# version_1.net
KiCad netlist of a schematic drawn in EAGLE
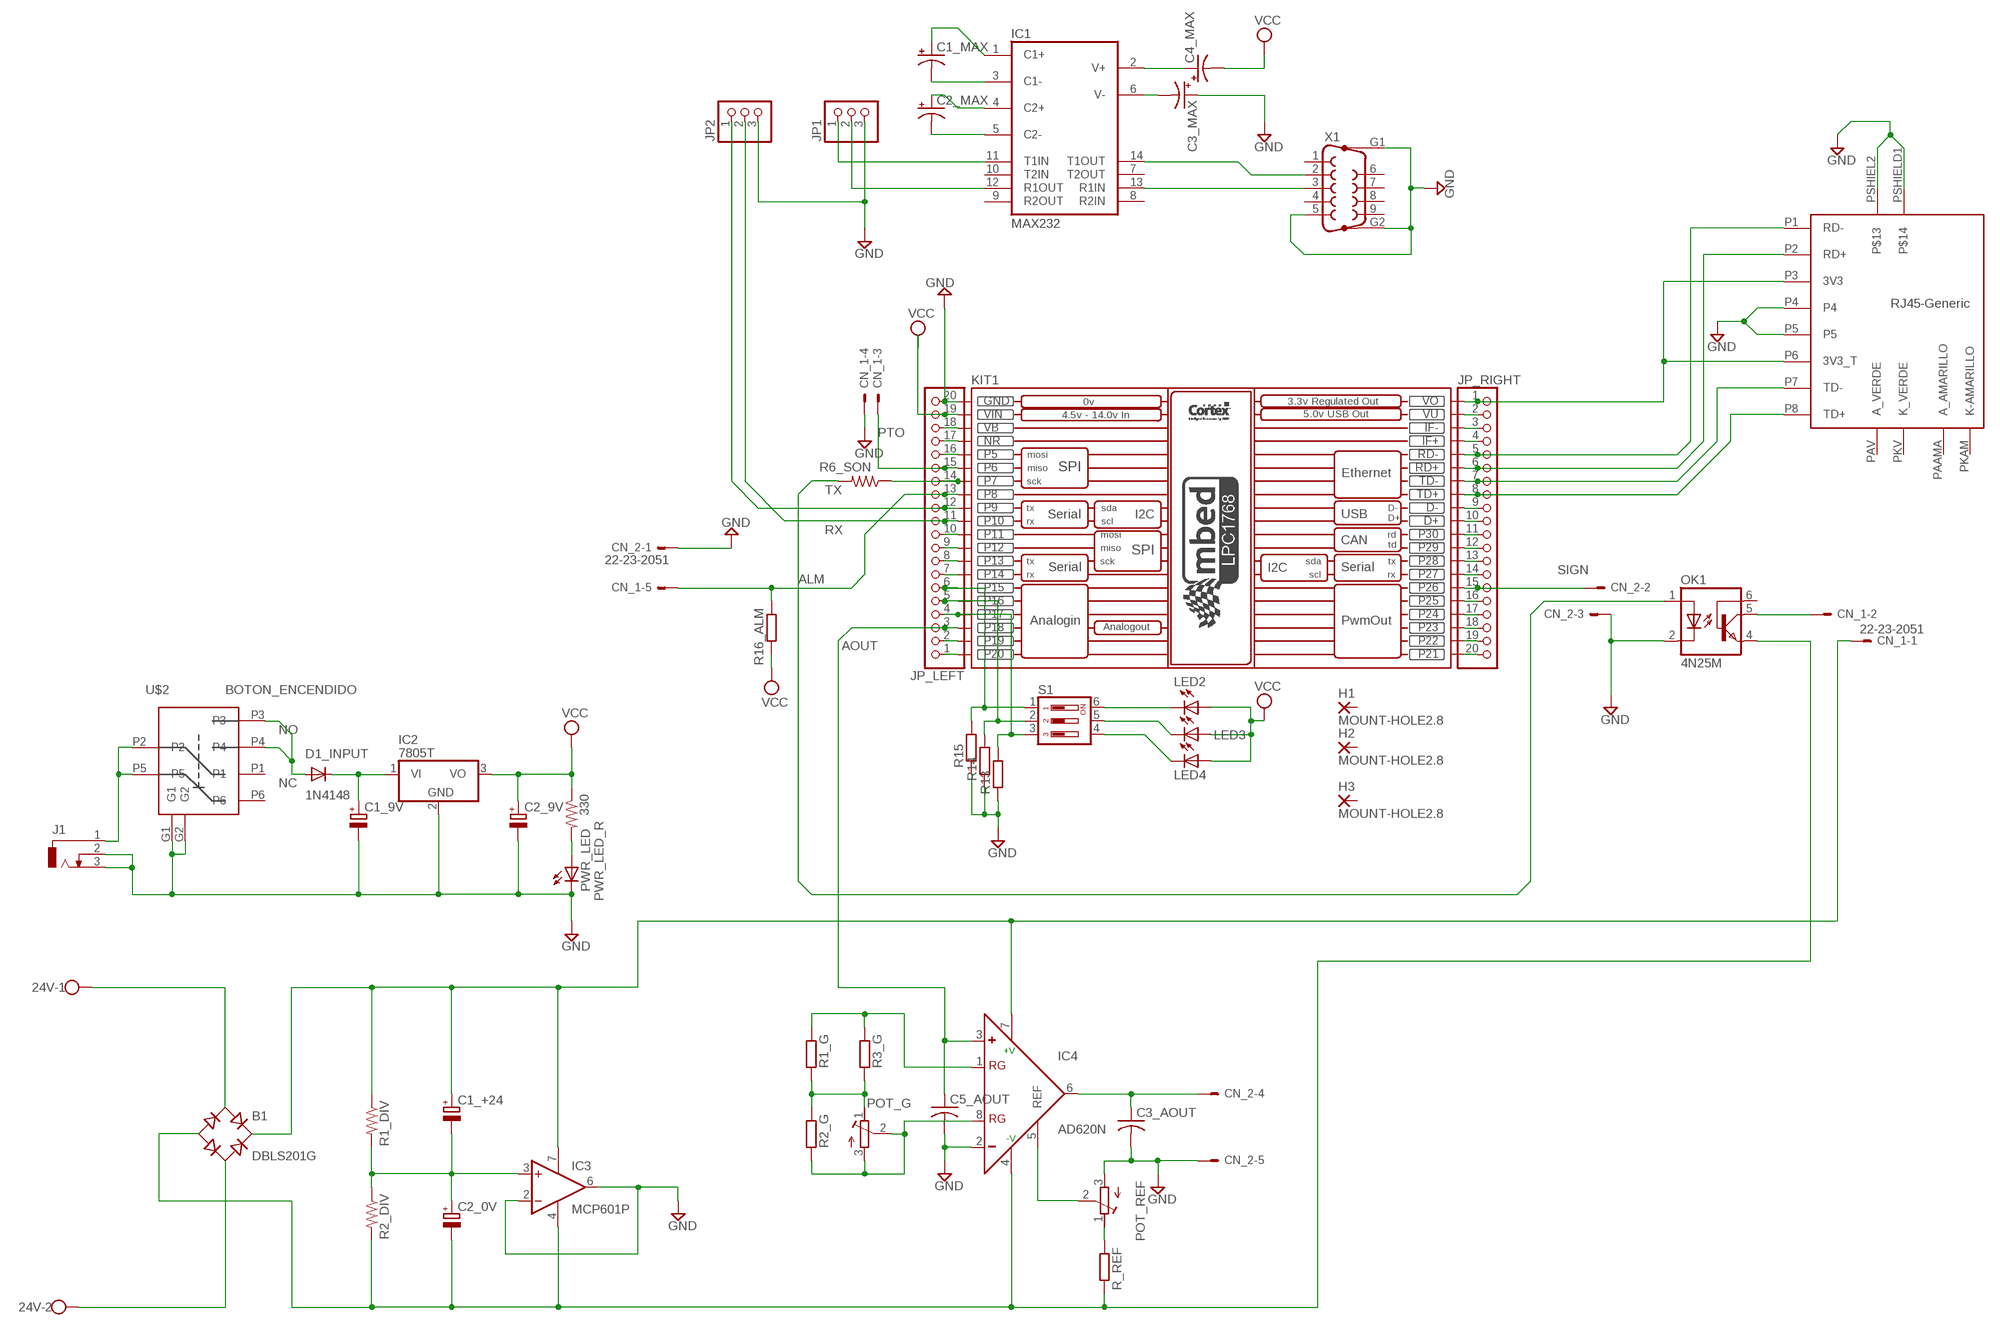
[diagram p0: schematic, sheet 1]

(export (version "E")
  (design (tool "Eeschema 10.0.6"))
  (components
    (comp (ref "24V")
      (value "W237-02P")
      (footprint "eagle-import:W237-132")
      (libsource (lib "eagle-import") (part "W237-02P"))
    )
    (comp (ref "B1")
      (value "DBLS201G")
      (footprint "eagle-import:DBS")
      (libsource (lib "eagle-import") (part "DB?GLS201"))
    )
    (comp (ref "C1_+24")
      (value "CPOL-EUTT5D7")
      (footprint "eagle-import:TT5D7")
      (libsource (lib "eagle-import") (part "CPOL-EUTT5D7"))
    )
    (comp (ref "C1_9V")
      (value "CPOL-EUTT5D7")
      (footprint "eagle-import:TT5D7")
      (libsource (lib "eagle-import") (part "CPOL-EUTT5D7"))
    )
    (comp (ref "C1_MAX")
      (value "CPOL-USE2,5-6E")
      (footprint "eagle-import:E2,5-6E")
      (libsource (lib "eagle-import") (part "CPOL-USE2,5-6E"))
    )
    (comp (ref "C2_0V")
      (value "CPOL-EUTT5D7")
      (footprint "eagle-import:TT5D7")
      (libsource (lib "eagle-import") (part "CPOL-EUTT5D7"))
    )
    (comp (ref "C2_9V")
      (value "CPOL-EUTT5D7")
      (footprint "eagle-import:TT5D7")
      (libsource (lib "eagle-import") (part "CPOL-EUTT5D7"))
    )
    (comp (ref "C2_MAX")
      (value "CPOL-USE2,5-6E")
      (footprint "eagle-import:E2,5-6E")
      (libsource (lib "eagle-import") (part "CPOL-USE2,5-6E"))
    )
    (comp (ref "C3_AOUT")
      (value "C-US025-024X044")
      (footprint "eagle-import:C025-024X044")
      (libsource (lib "eagle-import") (part "C-US025-024X044"))
    )
    (comp (ref "C3_MAX")
      (value "CPOL-USE2,5-6E")
      (footprint "eagle-import:E2,5-6E")
      (libsource (lib "eagle-import") (part "CPOL-USE2,5-6E"))
    )
    (comp (ref "C4_MAX")
      (value "CPOL-USE2,5-6E")
      (footprint "eagle-import:E2,5-6E")
      (libsource (lib "eagle-import") (part "CPOL-USE2,5-6E"))
    )
    (comp (ref "C5_AOUT")
      (value "C-US025-024X044")
      (footprint "eagle-import:C025-024X044")
      (libsource (lib "eagle-import") (part "C-US025-024X044"))
    )
    (comp (ref "CN_1")
      (value "22-23-2051")
      (footprint "eagle-import:22-23-2051")
      (libsource (lib "eagle-import") (part "22-23-2051"))
    )
    (comp (ref "CN_2")
      (value "22-23-2051")
      (footprint "eagle-import:22-23-2051")
      (libsource (lib "eagle-import") (part "22-23-2051"))
    )
    (comp (ref "D1_INPUT")
      (value "1N4148")
      (footprint "eagle-import:DO35-10")
      (libsource (lib "eagle-import") (part "1N4148DO35-10"))
    )
    (comp (ref "H1")
      (value "MOUNT-HOLE2.8")
      (footprint "eagle-import:2,54_0,8")
      (libsource (lib "eagle-import") (part "2,54/0,8"))
    )
    (comp (ref "H2")
      (value "MOUNT-HOLE2.8")
      (footprint "eagle-import:2,54_0,8")
      (libsource (lib "eagle-import") (part "2,54/0,8"))
    )
    (comp (ref "H3")
      (value "MOUNT-HOLE2.8")
      (footprint "eagle-import:2,54_0,8")
      (libsource (lib "eagle-import") (part "2,54/0,8"))
    )
    (comp (ref "IC1")
      (value "MAX232")
      (footprint "eagle-import:DIL16")
      (libsource (lib "eagle-import") (part "MAX232"))
    )
    (comp (ref "IC2")
      (value "7805T")
      (footprint "eagle-import:TO220H")
      (libsource (lib "eagle-import") (part "78T05"))
    )
    (comp (ref "IC3")
      (value "MCP601P")
      (footprint "eagle-import:DIL08")
      (libsource (lib "eagle-import") (part "MCP601P"))
    )
    (comp (ref "IC4")
      (value "AD620N")
      (footprint "eagle-import:DIL08")
      (libsource (lib "eagle-import") (part "AD620N"))
    )
    (comp (ref "J1")
      (value "DCJ0303")
      (footprint "eagle-import:DCJ0303")
      (libsource (lib "eagle-import") (part "DCJ0303"))
    )
    (comp (ref "JP1")
      (value "PINHD-1X3")
      (footprint "eagle-import:1X03")
      (libsource (lib "eagle-import") (part "PINHD-1X3"))
    )
    (comp (ref "JP2")
      (value "PINHD-1X3")
      (footprint "eagle-import:1X03")
      (libsource (lib "eagle-import") (part "PINHD-1X3"))
    )
    (comp (ref "JP_LEFT")
      (value "PINHD-1X20")
      (footprint "eagle-import:1X20")
      (libsource (lib "eagle-import") (part "PINHD-1X20"))
    )
    (comp (ref "JP_RIGHT")
      (value "PINHD-1X20")
      (footprint "eagle-import:1X20")
      (libsource (lib "eagle-import") (part "PINHD-1X20"))
    )
    (comp (ref "KIT1")
      (value "MBED_NXP_LPC1768")
      (footprint "eagle-import:MBED-KIT")
      (libsource (lib "eagle-import") (part "MBED_NXP_LPC1768"))
    )
    (comp (ref "LED2")
      (value "LED3MM")
      (footprint "eagle-import:LED3MM")
      (libsource (lib "eagle-import") (part "LED3MM"))
    )
    (comp (ref "LED3")
      (value "LED3MM")
      (footprint "eagle-import:LED3MM")
      (libsource (lib "eagle-import") (part "LED3MM"))
    )
    (comp (ref "LED4")
      (value "LED3MM")
      (footprint "eagle-import:LED3MM")
      (libsource (lib "eagle-import") (part "LED3MM"))
    )
    (comp (ref "OK1")
      (value "4N25M")
      (footprint "eagle-import:DIL06")
      (libsource (lib "eagle-import") (part "4N?M25"))
    )
    (comp (ref "POT_G")
      (value "R-TRIMMT93XB")
      (footprint "eagle-import:RTRIMT93XB")
      (libsource (lib "eagle-import") (part "R-TRIMMT93XB"))
    )
    (comp (ref "POT_REF")
      (value "R-TRIMMT93XB")
      (footprint "eagle-import:RTRIMT93XB")
      (libsource (lib "eagle-import") (part "R-TRIMMT93XB"))
    )
    (comp (ref "PWR_LED")
      (value "LED3MM")
      (footprint "eagle-import:LED3MM")
      (libsource (lib "eagle-import") (part "LED3MM"))
    )
    (comp (ref "PWR_LED_R")
      (value "330")
      (footprint "eagle-import:0207_15")
      (libsource (lib "eagle-import") (part "R-US_0207/15"))
    )
    (comp (ref "R1_DIV")
      (value "R-US_0207/10")
      (footprint "eagle-import:0207_10")
      (libsource (lib "eagle-import") (part "resistor_R-US_0207/10"))
    )
    (comp (ref "R1_G")
      (value "R-EU_0207/2V")
      (footprint "eagle-import:0207_2V")
      (libsource (lib "eagle-import") (part "R-EU_0207/2V"))
    )
    (comp (ref "R2_DIV")
      (value "R-US_0207/10")
      (footprint "eagle-import:0207_10")
      (libsource (lib "eagle-import") (part "resistor_R-US_0207/10"))
    )
    (comp (ref "R2_G")
      (value "R-EU_0207/2V")
      (footprint "eagle-import:0207_2V")
      (libsource (lib "eagle-import") (part "R-EU_0207/2V"))
    )
    (comp (ref "R3_G")
      (value "R-EU_0207/2V")
      (footprint "eagle-import:0207_2V")
      (libsource (lib "eagle-import") (part "R-EU_0207/2V"))
    )
    (comp (ref "R6_SON")
      (value "R-US_0207/7")
      (footprint "eagle-import:0207_7")
      (libsource (lib "eagle-import") (part "R-US_0207/7"))
    )
    (comp (ref "R13")
      (value "R-EU_0207/15")
      (footprint "eagle-import:0207_15")
      (libsource (lib "eagle-import") (part "R-EU_0207/15"))
    )
    (comp (ref "R14")
      (value "R-EU_0207/15")
      (footprint "eagle-import:0207_15")
      (libsource (lib "eagle-import") (part "R-EU_0207/15"))
    )
    (comp (ref "R15")
      (value "R-EU_0207/15")
      (footprint "eagle-import:0207_15")
      (libsource (lib "eagle-import") (part "R-EU_0207/15"))
    )
    (comp (ref "R16_ALM")
      (value "R-EU_0207/12")
      (footprint "eagle-import:0207_12")
      (libsource (lib "eagle-import") (part "R-EU_0207/12"))
    )
    (comp (ref "R_REF")
      (value "R-EU_0207/2V")
      (footprint "eagle-import:0207_2V")
      (libsource (lib "eagle-import") (part "R-EU_0207/2V"))
    )
    (comp (ref "S1")
      (value "DIP03YL")
      (footprint "eagle-import:DIP03YL")
      (libsource (lib "eagle-import") (part "DIP03YL"))
    )
    (comp (ref "U$1")
      (value "RJ-45-GENERIC")
      (footprint "eagle-import:RJ45-GENERIC")
      (libsource (lib "eagle-import") (part "RJ-45-GENERIC"))
    )
    (comp (ref "U$2")
      (value "BOTON_ENCENDIDO")
      (footprint "eagle-import:BOTON_ENCNEDIDO")
      (libsource (lib "eagle-import") (part "BOTON_ENCENDIDO"))
    )
    (comp (ref "X1")
      (value "F09HP")
      (footprint "eagle-import:F09HP")
      (libsource (lib "eagle-import") (part "F09HP"))
    )
  )
  (nets
    (net (code "1") (name "/ALM") (class "Default")
      (node (ref "CN_1") (pin "5") (pinfunction "S_5") (pintype "passive"))
      (node (ref "JP_LEFT") (pin "13") (pinfunction "13_13") (pintype "passive"))
      (node (ref "KIT1") (pin "P$8") (pinfunction "P8_P$8") (pintype "bidirectional"))
      (node (ref "R16_ALM") (pin "1") (pinfunction "1_1") (pintype "passive"))
    )
    (net (code "2") (name "/AOUT") (class "Default")
      (node (ref "C5_AOUT") (pin "1") (pinfunction "1_1") (pintype "passive"))
      (node (ref "IC4") (pin "3") (pinfunction "+_3") (pintype "input"))
      (node (ref "JP_LEFT") (pin "3") (pinfunction "3_3") (pintype "passive"))
      (node (ref "KIT1") (pin "P$18") (pinfunction "P18_P$18") (pintype "bidirectional"))
    )
    (net (code "3") (name "/PTO") (class "Default")
      (node (ref "CN_1") (pin "3") (pinfunction "S_3") (pintype "passive"))
      (node (ref "JP_LEFT") (pin "15") (pinfunction "15_15") (pintype "passive"))
      (node (ref "KIT1") (pin "P$6") (pinfunction "P6_P$6") (pintype "bidirectional"))
    )
    (net (code "4") (name "/RX") (class "Default")
      (node (ref "JP2") (pin "2") (pinfunction "2_2") (pintype "passive"))
      (node (ref "JP_LEFT") (pin "11") (pinfunction "11_11") (pintype "passive"))
      (node (ref "KIT1") (pin "P$10") (pinfunction "P10_P$10") (pintype "bidirectional"))
    )
    (net (code "5") (name "/SIGN") (class "Default")
      (node (ref "CN_2") (pin "2") (pinfunction "S_2") (pintype "passive"))
      (node (ref "JP_RIGHT") (pin "15") (pinfunction "15_15") (pintype "passive"))
      (node (ref "KIT1") (pin "P$26") (pinfunction "P26_P$26") (pintype "bidirectional"))
    )
    (net (code "6") (name "/TX") (class "Default")
      (node (ref "JP2") (pin "1") (pinfunction "1_1") (pintype "passive"))
      (node (ref "JP_LEFT") (pin "12") (pinfunction "12_12") (pintype "passive"))
      (node (ref "KIT1") (pin "P$9") (pinfunction "P9_P$9") (pintype "bidirectional"))
    )
    (net (code "7") (name "GND") (class "Default")
      (node (ref "C1_9V") (pin "-") (pinfunction "-_-") (pintype "passive"))
      (node (ref "C2_9V") (pin "-") (pinfunction "-_-") (pintype "passive"))
      (node (ref "C3_AOUT") (pin "2") (pinfunction "2_2") (pintype "passive"))
      (node (ref "C3_MAX") (pin "+") (pinfunction "+_+") (pintype "passive"))
      (node (ref "C5_AOUT") (pin "2") (pinfunction "2_2") (pintype "passive"))
      (node (ref "CN_1") (pin "4") (pinfunction "S_4") (pintype "passive"))
      (node (ref "CN_2") (pin "1") (pinfunction "S_1") (pintype "passive"))
      (node (ref "CN_2") (pin "3") (pinfunction "S_3") (pintype "passive"))
      (node (ref "CN_2") (pin "5") (pinfunction "S_5") (pintype "passive"))
      (node (ref "IC2") (pin "2") (pinfunction "GND_2") (pintype "passive"))
      (node (ref "IC3") (pin "2") (pinfunction "-IN_2") (pintype "input"))
      (node (ref "IC3") (pin "6") (pinfunction "OUT_6") (pintype "output"))
      (node (ref "IC4") (pin "2") (pinfunction "-_2") (pintype "input"))
      (node (ref "J1") (pin "2") (pinfunction "2_2") (pintype "passive"))
      (node (ref "J1") (pin "3") (pinfunction "3_3") (pintype "passive"))
      (node (ref "JP1") (pin "3") (pinfunction "3_3") (pintype "passive"))
      (node (ref "JP2") (pin "3") (pinfunction "3_3") (pintype "passive"))
      (node (ref "JP_LEFT") (pin "20") (pinfunction "20_20") (pintype "passive"))
      (node (ref "KIT1") (pin "GND") (pinfunction "GND_GND") (pintype "power_in"))
      (node (ref "OK1") (pin "2") (pinfunction "C_2") (pintype "passive"))
      (node (ref "POT_REF") (pin "3") (pinfunction "E_3") (pintype "passive"))
      (node (ref "PWR_LED") (pin "K") (pinfunction "C_K") (pintype "passive"))
      (node (ref "R13") (pin "1") (pinfunction "1_1") (pintype "passive"))
      (node (ref "R14") (pin "1") (pinfunction "1_1") (pintype "passive"))
      (node (ref "R15") (pin "1") (pinfunction "1_1") (pintype "passive"))
      (node (ref "U$1") (pin "P4") (pinfunction "P4_P4") (pintype "bidirectional"))
      (node (ref "U$1") (pin "P5") (pinfunction "P5_P5") (pintype "bidirectional"))
      (node (ref "U$1") (pin "PSHIEL2") (pinfunction "P$13_PSHIEL2") (pintype "bidirectional"))
      (node (ref "U$1") (pin "PSHIELD1") (pinfunction "P$14_PSHIELD1") (pintype "bidirectional"))
      (node (ref "U$2") (pin "G1") (pinfunction "G1_G1") (pintype "bidirectional"))
      (node (ref "U$2") (pin "G2") (pinfunction "G2_G2") (pintype "bidirectional"))
      (node (ref "X1") (pin "5") (pinfunction "5_5") (pintype "passive"))
      (node (ref "X1") (pin "G1") (pinfunction "G1_G1") (pintype "passive"))
      (node (ref "X1") (pin "G2") (pinfunction "G2_G2") (pintype "passive"))
    )
    (net (code "8") (name "Net-(24VA-KL)") (class "Default")
      (node (ref "24V") (pin "1") (pinfunction "KL_1") (pintype "passive"))
      (node (ref "B1") (pin "AC1") (pinfunction "AC1_AC1") (pintype "passive"))
    )
    (net (code "9") (name "Net-(24VB-KL)") (class "Default")
      (node (ref "24V") (pin "2") (pinfunction "KL_2") (pintype "passive"))
      (node (ref "B1") (pin "AC2") (pinfunction "AC2_AC2") (pintype "passive"))
    )
    (net (code "10") (name "Net-(CN_1A-S)") (class "Default")
      (node (ref "B1") (pin "+") (pinfunction "+_+") (pintype "passive"))
      (node (ref "C1_+24") (pin "+") (pinfunction "+_+") (pintype "passive"))
      (node (ref "CN_1") (pin "1") (pinfunction "S_1") (pintype "passive"))
      (node (ref "IC3") (pin "7") (pinfunction "V+_7") (pintype "power_in"))
      (node (ref "IC4") (pin "7") (pinfunction "+V_7") (pintype "power_in"))
      (node (ref "R1_DIV") (pin "1") (pinfunction "1_1") (pintype "passive"))
    )
    (net (code "11") (name "Net-(CN_1B-S)") (class "Default")
      (node (ref "CN_1") (pin "2") (pinfunction "S_2") (pintype "passive"))
      (node (ref "OK1") (pin "5") (pinfunction "COL_5") (pintype "passive"))
    )
    (net (code "12") (name "Net-(CN_2D-S)") (class "Default")
      (node (ref "C3_AOUT") (pin "1") (pinfunction "1_1") (pintype "passive"))
      (node (ref "CN_2") (pin "4") (pinfunction "S_4") (pintype "passive"))
      (node (ref "IC4") (pin "6") (pinfunction "OUT_6") (pintype "output"))
    )
    (net (code "13") (name "Net-(D1_INPUT-PadA)") (class "Default")
      (node (ref "D1_INPUT") (pin "A") (pinfunction "A_A") (pintype "passive"))
      (node (ref "U$2") (pin "P3") (pinfunction "P3_P3") (pintype "bidirectional"))
      (node (ref "U$2") (pin "P4") (pinfunction "P4_P4") (pintype "bidirectional"))
    )
    (net (code "14") (name "Net-(IC1A-C1+)") (class "Default")
      (node (ref "C1_MAX") (pin "+") (pinfunction "+_+") (pintype "passive"))
      (node (ref "IC1") (pin "1") (pinfunction "C1+_1") (pintype "bidirectional"))
    )
    (net (code "15") (name "Net-(IC1A-C1-)") (class "Default")
      (node (ref "C1_MAX") (pin "-") (pinfunction "-_-") (pintype "passive"))
      (node (ref "IC1") (pin "3") (pinfunction "C1-_3") (pintype "bidirectional"))
    )
    (net (code "16") (name "Net-(IC1A-C2+)") (class "Default")
      (node (ref "C2_MAX") (pin "+") (pinfunction "+_+") (pintype "passive"))
      (node (ref "IC1") (pin "4") (pinfunction "C2+_4") (pintype "bidirectional"))
    )
    (net (code "17") (name "Net-(IC1A-C2-)") (class "Default")
      (node (ref "C2_MAX") (pin "-") (pinfunction "-_-") (pintype "passive"))
      (node (ref "IC1") (pin "5") (pinfunction "C2-_5") (pintype "bidirectional"))
    )
    (net (code "18") (name "Net-(IC1A-R1IN)") (class "Default")
      (node (ref "IC1") (pin "13") (pinfunction "R1IN_13") (pintype "input"))
      (node (ref "X1") (pin "3") (pinfunction "3_3") (pintype "passive"))
    )
    (net (code "19") (name "Net-(IC1A-R1OUT)") (class "Default")
      (node (ref "IC1") (pin "12") (pinfunction "R1OUT_12") (pintype "output"))
      (node (ref "JP1") (pin "2") (pinfunction "2_2") (pintype "passive"))
    )
    (net (code "20") (name "Net-(IC1A-T1IN)") (class "Default")
      (node (ref "IC1") (pin "11") (pinfunction "T1IN_11") (pintype "input"))
      (node (ref "JP1") (pin "1") (pinfunction "1_1") (pintype "passive"))
    )
    (net (code "21") (name "Net-(IC1A-T1OUT)") (class "Default")
      (node (ref "IC1") (pin "14") (pinfunction "T1OUT_14") (pintype "output"))
      (node (ref "X1") (pin "2") (pinfunction "2_2") (pintype "passive"))
    )
    (net (code "22") (name "Net-(IC1A-V+)") (class "Default")
      (node (ref "C4_MAX") (pin "+") (pinfunction "+_+") (pintype "passive"))
      (node (ref "IC1") (pin "2") (pinfunction "V+_2") (pintype "bidirectional"))
    )
    (net (code "23") (name "Net-(IC1A-V-)") (class "Default")
      (node (ref "C3_MAX") (pin "-") (pinfunction "-_-") (pintype "passive"))
      (node (ref "IC1") (pin "6") (pinfunction "V-_6") (pintype "bidirectional"))
    )
    (net (code "24") (name "Net-(IC2-VI)") (class "Default")
      (node (ref "C1_9V") (pin "+") (pinfunction "+_+") (pintype "passive"))
      (node (ref "D1_INPUT") (pin "C") (pinfunction "C_C") (pintype "passive"))
      (node (ref "IC2") (pin "1") (pinfunction "VI_1") (pintype "input"))
    )
    (net (code "25") (name "Net-(IC3-+IN)") (class "Default")
      (node (ref "C1_+24") (pin "-") (pinfunction "-_-") (pintype "passive"))
      (node (ref "C2_0V") (pin "+") (pinfunction "+_+") (pintype "passive"))
      (node (ref "IC3") (pin "3") (pinfunction "+IN_3") (pintype "input"))
      (node (ref "R1_DIV") (pin "2") (pinfunction "2_2") (pintype "passive"))
      (node (ref "R2_DIV") (pin "1") (pinfunction "1_1") (pintype "passive"))
    )
    (net (code "26") (name "Net-(IC3-V-)") (class "Default")
      (node (ref "B1") (pin "-") (pinfunction "-_-") (pintype "passive"))
      (node (ref "C2_0V") (pin "-") (pinfunction "-_-") (pintype "passive"))
      (node (ref "IC3") (pin "4") (pinfunction "V-_4") (pintype "power_in"))
      (node (ref "IC4") (pin "4") (pinfunction "-V_4") (pintype "power_in"))
      (node (ref "OK1") (pin "4") (pinfunction "EMI_4") (pintype "passive"))
      (node (ref "R2_DIV") (pin "2") (pinfunction "2_2") (pintype "passive"))
      (node (ref "R_REF") (pin "2") (pinfunction "2_2") (pintype "passive"))
    )
    (net (code "27") (name "Net-(IC4-REF)") (class "Default")
      (node (ref "IC4") (pin "5") (pinfunction "REF_5") (pintype "passive"))
      (node (ref "POT_REF") (pin "2") (pinfunction "S_2") (pintype "passive"))
    )
    (net (code "28") (name "Net-(IC4-RG-Pad1)") (class "Default")
      (node (ref "IC4") (pin "1") (pinfunction "RG_1") (pintype "passive"))
      (node (ref "R1_G") (pin "1") (pinfunction "1_1") (pintype "passive"))
      (node (ref "R3_G") (pin "1") (pinfunction "1_1") (pintype "passive"))
    )
    (net (code "29") (name "Net-(J1-Pad1)") (class "Default")
      (node (ref "J1") (pin "1") (pinfunction "1_1") (pintype "passive"))
      (node (ref "U$2") (pin "P2") (pinfunction "P2_P2") (pintype "bidirectional"))
      (node (ref "U$2") (pin "P5") (pinfunction "P5_P5") (pintype "bidirectional"))
    )
    (net (code "30") (name "Net-(JP_LEFT-Pad17)") (class "Default")
      (node (ref "JP_LEFT") (pin "17") (pinfunction "17_17") (pintype "passive"))
      (node (ref "KIT1") (pin "NR") (pinfunction "NR_NR") (pintype "power_in"))
    )
    (net (code "31") (name "Net-(JP_LEFT-Pad18)") (class "Default")
      (node (ref "JP_LEFT") (pin "18") (pinfunction "18_18") (pintype "passive"))
      (node (ref "KIT1") (pin "VB") (pinfunction "VB_VB") (pintype "power_in"))
    )
    (net (code "32") (name "Net-(JP_RIGHT-Pad2)") (class "Default")
      (node (ref "JP_RIGHT") (pin "2") (pinfunction "2_2") (pintype "passive"))
      (node (ref "KIT1") (pin "VU") (pinfunction "VU_VU") (pintype "power_in"))
    )
    (net (code "33") (name "Net-(JP_RIGHT-Pad3)") (class "Default")
      (node (ref "JP_RIGHT") (pin "3") (pinfunction "3_3") (pintype "passive"))
      (node (ref "KIT1") (pin "IF-") (pinfunction "IF-_IF-") (pintype "bidirectional"))
    )
    (net (code "34") (name "Net-(JP_RIGHT-Pad4)") (class "Default")
      (node (ref "JP_RIGHT") (pin "4") (pinfunction "4_4") (pintype "passive"))
      (node (ref "KIT1") (pin "IF+") (pinfunction "IF+_IF+") (pintype "bidirectional"))
    )
    (net (code "35") (name "Net-(JP_RIGHT-Pad9)") (class "Default")
      (node (ref "JP_RIGHT") (pin "9") (pinfunction "9_9") (pintype "passive"))
      (node (ref "KIT1") (pin "D-") (pinfunction "D-_D-") (pintype "bidirectional"))
    )
    (net (code "36") (name "Net-(JP_RIGHT-Pad10)") (class "Default")
      (node (ref "JP_RIGHT") (pin "10") (pinfunction "10_10") (pintype "passive"))
      (node (ref "KIT1") (pin "D+") (pinfunction "D+_D+") (pintype "bidirectional"))
    )
    (net (code "37") (name "Net-(KIT1-P5)") (class "Default")
      (node (ref "JP_LEFT") (pin "16") (pinfunction "16_16") (pintype "passive"))
      (node (ref "KIT1") (pin "P$5") (pinfunction "P5_P$5") (pintype "bidirectional"))
    )
    (net (code "38") (name "Net-(KIT1-P7)") (class "Default")
      (node (ref "JP_LEFT") (pin "14") (pinfunction "14_14") (pintype "passive"))
      (node (ref "KIT1") (pin "P$7") (pinfunction "P7_P$7") (pintype "bidirectional"))
      (node (ref "R6_SON") (pin "1") (pinfunction "1_1") (pintype "passive"))
    )
    (net (code "39") (name "Net-(KIT1-P11)") (class "Default")
      (node (ref "JP_LEFT") (pin "10") (pinfunction "10_10") (pintype "passive"))
      (node (ref "KIT1") (pin "P$11") (pinfunction "P11_P$11") (pintype "bidirectional"))
    )
    (net (code "40") (name "Net-(KIT1-P12)") (class "Default")
      (node (ref "JP_LEFT") (pin "9") (pinfunction "9_9") (pintype "passive"))
      (node (ref "KIT1") (pin "P$12") (pinfunction "P12_P$12") (pintype "bidirectional"))
    )
    (net (code "41") (name "Net-(KIT1-P13)") (class "Default")
      (node (ref "JP_LEFT") (pin "8") (pinfunction "8_8") (pintype "passive"))
      (node (ref "KIT1") (pin "P$13") (pinfunction "P13_P$13") (pintype "bidirectional"))
    )
    (net (code "42") (name "Net-(KIT1-P14)") (class "Default")
      (node (ref "JP_LEFT") (pin "7") (pinfunction "7_7") (pintype "passive"))
      (node (ref "KIT1") (pin "P$14") (pinfunction "P14_P$14") (pintype "bidirectional"))
    )
    (net (code "43") (name "Net-(KIT1-P15)") (class "Default")
      (node (ref "JP_LEFT") (pin "6") (pinfunction "6_6") (pintype "passive"))
      (node (ref "KIT1") (pin "P$15") (pinfunction "P15_P$15") (pintype "bidirectional"))
      (node (ref "R15") (pin "2") (pinfunction "2_2") (pintype "passive"))
      (node (ref "S1") (pin "1") (pinfunction "1_1") (pintype "passive"))
    )
    (net (code "44") (name "Net-(KIT1-P16)") (class "Default")
      (node (ref "JP_LEFT") (pin "5") (pinfunction "5_5") (pintype "passive"))
      (node (ref "KIT1") (pin "P$16") (pinfunction "P16_P$16") (pintype "bidirectional"))
      (node (ref "R14") (pin "2") (pinfunction "2_2") (pintype "passive"))
      (node (ref "S1") (pin "2") (pinfunction "2_2") (pintype "passive"))
    )
    (net (code "45") (name "Net-(KIT1-P17)") (class "Default")
      (node (ref "JP_LEFT") (pin "4") (pinfunction "4_4") (pintype "passive"))
      (node (ref "KIT1") (pin "P$17") (pinfunction "P17_P$17") (pintype "bidirectional"))
      (node (ref "R13") (pin "2") (pinfunction "2_2") (pintype "passive"))
      (node (ref "S1") (pin "3") (pinfunction "3_3") (pintype "passive"))
    )
    (net (code "46") (name "Net-(KIT1-P19)") (class "Default")
      (node (ref "JP_LEFT") (pin "2") (pinfunction "2_2") (pintype "passive"))
      (node (ref "KIT1") (pin "P$19") (pinfunction "P19_P$19") (pintype "bidirectional"))
    )
    (net (code "47") (name "Net-(KIT1-P20)") (class "Default")
      (node (ref "JP_LEFT") (pin "1") (pinfunction "1_1") (pintype "passive"))
      (node (ref "KIT1") (pin "P$20") (pinfunction "P20_P$20") (pintype "bidirectional"))
    )
    (net (code "48") (name "Net-(KIT1-P21)") (class "Default")
      (node (ref "JP_RIGHT") (pin "20") (pinfunction "20_20") (pintype "passive"))
      (node (ref "KIT1") (pin "P$21") (pinfunction "P21_P$21") (pintype "bidirectional"))
    )
    (net (code "49") (name "Net-(KIT1-P22)") (class "Default")
      (node (ref "JP_RIGHT") (pin "19") (pinfunction "19_19") (pintype "passive"))
      (node (ref "KIT1") (pin "P$22") (pinfunction "P22_P$22") (pintype "bidirectional"))
    )
    (net (code "50") (name "Net-(KIT1-P23)") (class "Default")
      (node (ref "JP_RIGHT") (pin "18") (pinfunction "18_18") (pintype "passive"))
      (node (ref "KIT1") (pin "P$23") (pinfunction "P23_P$23") (pintype "bidirectional"))
    )
    (net (code "51") (name "Net-(KIT1-P24)") (class "Default")
      (node (ref "JP_RIGHT") (pin "17") (pinfunction "17_17") (pintype "passive"))
      (node (ref "KIT1") (pin "P$24") (pinfunction "P24_P$24") (pintype "bidirectional"))
    )
    (net (code "52") (name "Net-(KIT1-P25)") (class "Default")
      (node (ref "JP_RIGHT") (pin "16") (pinfunction "16_16") (pintype "passive"))
      (node (ref "KIT1") (pin "P$25") (pinfunction "P25_P$25") (pintype "bidirectional"))
    )
    (net (code "53") (name "Net-(KIT1-P27)") (class "Default")
      (node (ref "JP_RIGHT") (pin "14") (pinfunction "14_14") (pintype "passive"))
      (node (ref "KIT1") (pin "P$27") (pinfunction "P27_P$27") (pintype "bidirectional"))
    )
    (net (code "54") (name "Net-(KIT1-P28)") (class "Default")
      (node (ref "JP_RIGHT") (pin "13") (pinfunction "13_13") (pintype "passive"))
      (node (ref "KIT1") (pin "P$28") (pinfunction "P28_P$28") (pintype "bidirectional"))
    )
    (net (code "55") (name "Net-(KIT1-P29)") (class "Default")
      (node (ref "JP_RIGHT") (pin "12") (pinfunction "12_12") (pintype "passive"))
      (node (ref "KIT1") (pin "P$29") (pinfunction "P29_P$29") (pintype "bidirectional"))
    )
    (net (code "56") (name "Net-(KIT1-P30)") (class "Default")
      (node (ref "JP_RIGHT") (pin "11") (pinfunction "11_11") (pintype "passive"))
      (node (ref "KIT1") (pin "P$30") (pinfunction "P30_P$30") (pintype "bidirectional"))
    )
    (net (code "57") (name "Net-(KIT1-VO)") (class "Default")
      (node (ref "JP_RIGHT") (pin "1") (pinfunction "1_1") (pintype "passive"))
      (node (ref "KIT1") (pin "VOUT") (pinfunction "VO_VOUT") (pintype "power_in"))
      (node (ref "U$1") (pin "P3") (pinfunction "3V3_P3") (pintype "bidirectional"))
      (node (ref "U$1") (pin "P6") (pinfunction "3V3_T_P6") (pintype "bidirectional"))
    )
    (net (code "58") (name "Net-(LED2-C)") (class "Default")
      (node (ref "LED2") (pin "K") (pinfunction "C_K") (pintype "passive"))
      (node (ref "S1") (pin "6") (pinfunction "6_6") (pintype "passive"))
    )
    (net (code "59") (name "Net-(LED3-C)") (class "Default")
      (node (ref "LED3") (pin "K") (pinfunction "C_K") (pintype "passive"))
      (node (ref "S1") (pin "5") (pinfunction "5_5") (pintype "passive"))
    )
    (net (code "60") (name "Net-(LED4-C)") (class "Default")
      (node (ref "LED4") (pin "K") (pinfunction "C_K") (pintype "passive"))
      (node (ref "S1") (pin "4") (pinfunction "4_4") (pintype "passive"))
    )
    (net (code "61") (name "Net-(OK1-A)") (class "Default")
      (node (ref "OK1") (pin "1") (pinfunction "A_1") (pintype "passive"))
      (node (ref "R6_SON") (pin "2") (pinfunction "2_2") (pintype "passive"))
    )
    (net (code "62") (name "Net-(POT_G-A)") (class "Default")
      (node (ref "POT_G") (pin "1") (pinfunction "A_1") (pintype "passive"))
      (node (ref "R1_G") (pin "2") (pinfunction "2_2") (pintype "passive"))
      (node (ref "R2_G") (pin "1") (pinfunction "1_1") (pintype "passive"))
      (node (ref "R3_G") (pin "2") (pinfunction "2_2") (pintype "passive"))
    )
    (net (code "63") (name "Net-(POT_G-E)") (class "Default")
      (node (ref "IC4") (pin "8") (pinfunction "RG_8") (pintype "passive"))
      (node (ref "POT_G") (pin "2") (pinfunction "S_2") (pintype "passive"))
      (node (ref "POT_G") (pin "3") (pinfunction "E_3") (pintype "passive"))
      (node (ref "R2_G") (pin "2") (pinfunction "2_2") (pintype "passive"))
    )
    (net (code "64") (name "Net-(POT_REF-A)") (class "Default")
      (node (ref "POT_REF") (pin "1") (pinfunction "A_1") (pintype "passive"))
      (node (ref "R_REF") (pin "1") (pinfunction "1_1") (pintype "passive"))
    )
    (net (code "65") (name "Net-(PWR_LED-PadA)") (class "Default")
      (node (ref "PWR_LED") (pin "A") (pinfunction "A_A") (pintype "passive"))
      (node (ref "PWR_LED_R") (pin "2") (pinfunction "2_2") (pintype "passive"))
    )
    (net (code "66") (name "Net-(U$1-RD+)") (class "Default")
      (node (ref "JP_RIGHT") (pin "6") (pinfunction "6_6") (pintype "passive"))
      (node (ref "KIT1") (pin "RD+") (pinfunction "RD+_RD+") (pintype "bidirectional"))
      (node (ref "U$1") (pin "P2") (pinfunction "RD+_P2") (pintype "bidirectional"))
    )
    (net (code "67") (name "Net-(U$1-RD-)") (class "Default")
      (node (ref "JP_RIGHT") (pin "5") (pinfunction "5_5") (pintype "passive"))
      (node (ref "KIT1") (pin "RD-") (pinfunction "RD-_RD-") (pintype "bidirectional"))
      (node (ref "U$1") (pin "P1") (pinfunction "RD-_P1") (pintype "bidirectional"))
    )
    (net (code "68") (name "Net-(U$1-TD+)") (class "Default")
      (node (ref "JP_RIGHT") (pin "8") (pinfunction "8_8") (pintype "passive"))
      (node (ref "KIT1") (pin "TD+") (pinfunction "TD+_TD+") (pintype "bidirectional"))
      (node (ref "U$1") (pin "P8") (pinfunction "TD+_P8") (pintype "bidirectional"))
    )
    (net (code "69") (name "Net-(U$1-TD-)") (class "Default")
      (node (ref "JP_RIGHT") (pin "7") (pinfunction "7_7") (pintype "passive"))
      (node (ref "KIT1") (pin "TD-") (pinfunction "TD-_TD-") (pintype "bidirectional"))
      (node (ref "U$1") (pin "P7") (pinfunction "TD-_P7") (pintype "bidirectional"))
    )
    (net (code "70") (name "VCC") (class "Default")
      (node (ref "C2_9V") (pin "+") (pinfunction "+_+") (pintype "passive"))
      (node (ref "C4_MAX") (pin "-") (pinfunction "-_-") (pintype "passive"))
      (node (ref "IC2") (pin "3") (pinfunction "VO_3") (pintype "passive"))
      (node (ref "JP_LEFT") (pin "19") (pinfunction "19_19") (pintype "passive"))
      (node (ref "KIT1") (pin "VIN") (pinfunction "VIN_VIN") (pintype "power_in"))
      (node (ref "LED2") (pin "A") (pinfunction "A_A") (pintype "passive"))
      (node (ref "LED3") (pin "A") (pinfunction "A_A") (pintype "passive"))
      (node (ref "LED4") (pin "A") (pinfunction "A_A") (pintype "passive"))
      (node (ref "PWR_LED_R") (pin "1") (pinfunction "1_1") (pintype "passive"))
      (node (ref "R16_ALM") (pin "2") (pinfunction "2_2") (pintype "passive"))
    )
    (net (code "71") (name "unconnected-(H1-P-Pad1)") (class "Default")
      (node (ref "H1") (pin "1") (pinfunction "P_1") (pintype "passive"))
    )
    (net (code "72") (name "unconnected-(H2-P-Pad1)") (class "Default")
      (node (ref "H2") (pin "1") (pinfunction "P_1") (pintype "passive"))
    )
    (net (code "73") (name "unconnected-(H3-P-Pad1)") (class "Default")
      (node (ref "H3") (pin "1") (pinfunction "P_1") (pintype "passive"))
    )
    (net (code "74") (name "unconnected-(IC1A-R2IN-Pad8)") (class "Default")
      (node (ref "IC1") (pin "8") (pinfunction "R2IN_8") (pintype "input"))
    )
    (net (code "75") (name "unconnected-(IC1A-R2OUT-Pad9)") (class "Default")
      (node (ref "IC1") (pin "9") (pinfunction "R2OUT_9") (pintype "output"))
    )
    (net (code "76") (name "unconnected-(IC1A-T2IN-Pad10)") (class "Default")
      (node (ref "IC1") (pin "10") (pinfunction "T2IN_10") (pintype "input"))
    )
    (net (code "77") (name "unconnected-(IC1A-T2OUT-Pad7)") (class "Default")
      (node (ref "IC1") (pin "7") (pinfunction "T2OUT_7") (pintype "output"))
    )
    (net (code "78") (name "unconnected-(OK1-BAS-Pad6)") (class "Default")
      (node (ref "OK1") (pin "6") (pinfunction "BAS_6") (pintype "passive"))
    )
    (net (code "79") (name "unconnected-(U$1-A_AMARILLO-PadPAAMA)") (class "Default")
      (node (ref "U$1") (pin "PAAMA") (pinfunction "A_AMARILLO_PAAMA") (pintype "bidirectional"))
    )
    (net (code "80") (name "unconnected-(U$1-A_VERDE-PadPAV)") (class "Default")
      (node (ref "U$1") (pin "PAV") (pinfunction "A_VERDE_PAV") (pintype "bidirectional"))
    )
    (net (code "81") (name "unconnected-(U$1-K-AMARILLO-PadPKAM)") (class "Default")
      (node (ref "U$1") (pin "PKAM") (pinfunction "K-AMARILLO_PKAM") (pintype "bidirectional"))
    )
    (net (code "82") (name "unconnected-(U$1-K_VERDE-PadPKV)") (class "Default")
      (node (ref "U$1") (pin "PKV") (pinfunction "K_VERDE_PKV") (pintype "bidirectional"))
    )
    (net (code "83") (name "unconnected-(U$2-PadP1)") (class "Default")
      (node (ref "U$2") (pin "P1") (pinfunction "P1_P1") (pintype "bidirectional"))
    )
    (net (code "84") (name "unconnected-(U$2-PadP6)") (class "Default")
      (node (ref "U$2") (pin "P6") (pinfunction "P6_P6") (pintype "bidirectional"))
    )
    (net (code "85") (name "unconnected-(X1-Pad1)") (class "Default")
      (node (ref "X1") (pin "1") (pinfunction "1_1") (pintype "passive"))
    )
    (net (code "86") (name "unconnected-(X1-Pad4)") (class "Default")
      (node (ref "X1") (pin "4") (pinfunction "4_4") (pintype "passive"))
    )
    (net (code "87") (name "unconnected-(X1-Pad6)") (class "Default")
      (node (ref "X1") (pin "6") (pinfunction "6_6") (pintype "passive"))
    )
    (net (code "88") (name "unconnected-(X1-Pad7)") (class "Default")
      (node (ref "X1") (pin "7") (pinfunction "7_7") (pintype "passive"))
    )
    (net (code "89") (name "unconnected-(X1-Pad8)") (class "Default")
      (node (ref "X1") (pin "8") (pinfunction "8_8") (pintype "passive"))
    )
    (net (code "90") (name "unconnected-(X1-Pad9)") (class "Default")
      (node (ref "X1") (pin "9") (pinfunction "9_9") (pintype "passive"))
    )
  )
)
